# STM32.net
KiCad netlist of a schematic drawn in Altium Designer
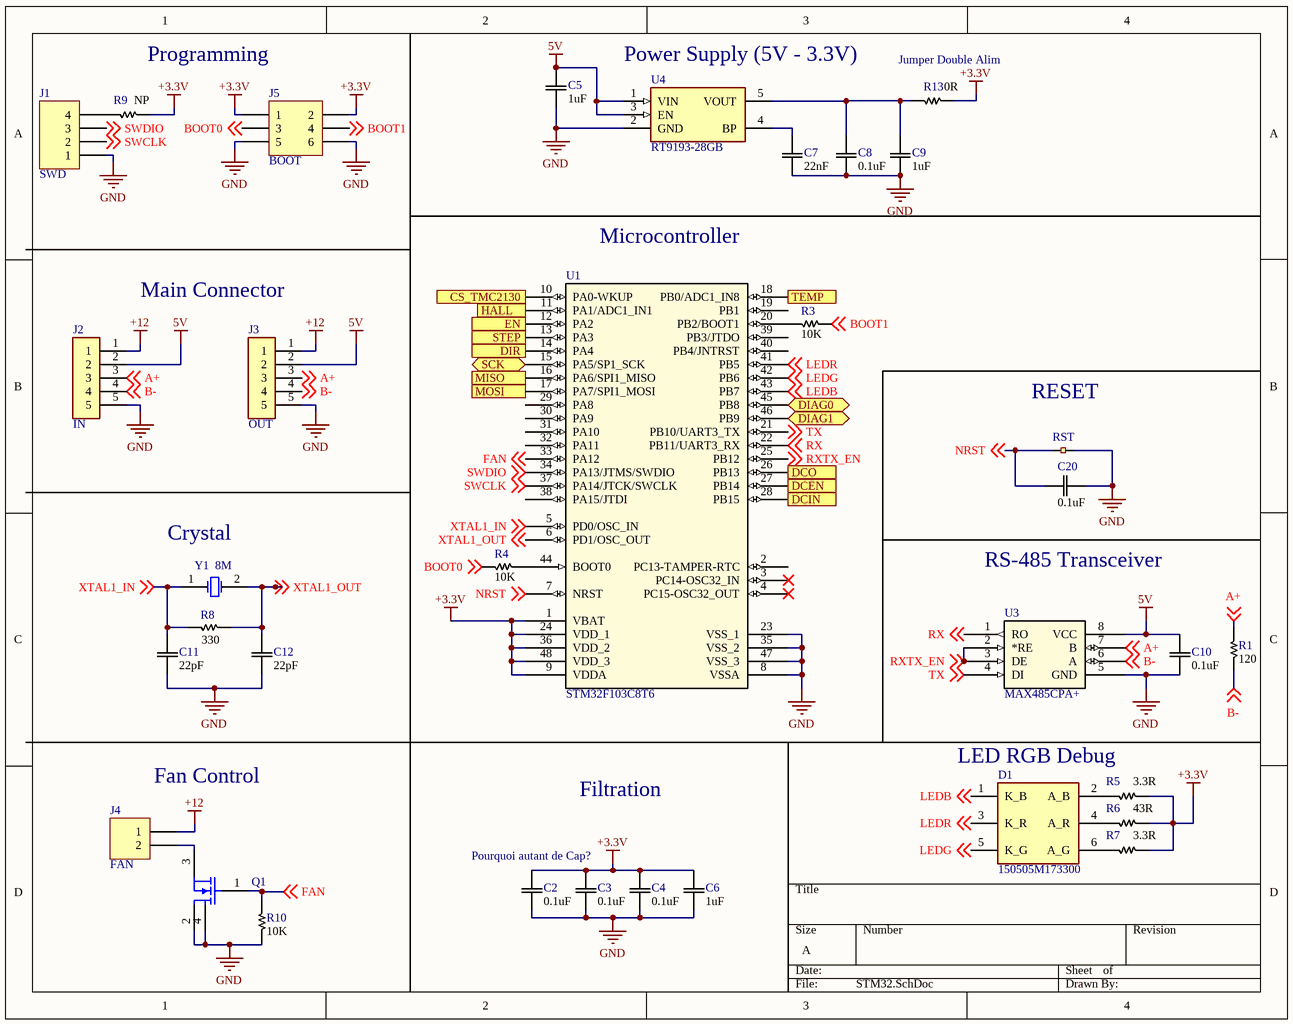
[diagram p0: STM32.SchDoc]

(export (version "E")
  (design (tool "Eeschema 10.0.6"))
  (components
    (comp (ref "C2")
      (value "0.1uF")
      (footprint "0603")
      (description "Capacitor SMD 1206")
      (fields
        (field (name "MANUFACTURER_PART_NUMBER") "12065A820JAT2A")
        (field (name "Comment") "Capacitor 1206")
        (field (name "COPYRIGHT") "Copyright (C) 2018 Accelerated Designs. All rights reserved")
      )
      (libsource (lib "Schematic_Emile") (part "Capacitor 1206"))
    )
    (comp (ref "C3")
      (value "0.1uF")
      (footprint "0603")
      (description "Capacitor SMD 1206")
      (fields
        (field (name "MANUFACTURER_PART_NUMBER") "12065A820JAT2A")
        (field (name "Comment") "Capacitor 1206")
        (field (name "COPYRIGHT") "Copyright (C) 2018 Accelerated Designs. All rights reserved")
      )
      (libsource (lib "Schematic_Emile") (part "Capacitor 1206"))
    )
    (comp (ref "C4")
      (value "0.1uF")
      (footprint "0603")
      (description "Capacitor SMD 1206")
      (fields
        (field (name "MANUFACTURER_PART_NUMBER") "12065A820JAT2A")
        (field (name "Comment") "Capacitor 1206")
        (field (name "COPYRIGHT") "Copyright (C) 2018 Accelerated Designs. All rights reserved")
      )
      (libsource (lib "Schematic_Emile") (part "Capacitor 1206"))
    )
    (comp (ref "C5")
      (value "1uF")
      (footprint "0603")
      (description "Capacitor SMD 1206")
      (fields
        (field (name "MANUFACTURER_PART_NUMBER") "12065A820JAT2A")
        (field (name "Comment") "Capacitor 1206")
        (field (name "COPYRIGHT") "Copyright (C) 2018 Accelerated Designs. All rights reserved")
      )
      (libsource (lib "Schematic_Emile") (part "Capacitor 1206"))
    )
    (comp (ref "C6")
      (value "1uF")
      (footprint "0603")
      (description "Capacitor SMD 1206")
      (fields
        (field (name "MANUFACTURER_PART_NUMBER") "12065A820JAT2A")
        (field (name "Comment") "Capacitor 1206")
        (field (name "COPYRIGHT") "Copyright (C) 2018 Accelerated Designs. All rights reserved")
      )
      (libsource (lib "Schematic_Emile") (part "Capacitor 1206"))
    )
    (comp (ref "C7")
      (value "22nF")
      (footprint "0603")
      (description "Capacitor SMD 1206")
      (fields
        (field (name "MANUFACTURER_PART_NUMBER") "12065A820JAT2A")
        (field (name "Comment") "Capacitor 1206")
        (field (name "COPYRIGHT") "Copyright (C) 2018 Accelerated Designs. All rights reserved")
      )
      (libsource (lib "Schematic_Emile") (part "Capacitor 1206"))
    )
    (comp (ref "C8")
      (value "0.1uF")
      (footprint "0603")
      (description "Capacitor SMD 1206")
      (fields
        (field (name "MANUFACTURER_PART_NUMBER") "12065A820JAT2A")
        (field (name "Comment") "Capacitor 1206")
        (field (name "COPYRIGHT") "Copyright (C) 2018 Accelerated Designs. All rights reserved")
      )
      (libsource (lib "Schematic_Emile") (part "Capacitor 1206"))
    )
    (comp (ref "C9")
      (value "1uF")
      (footprint "0603")
      (description "Capacitor SMD 1206")
      (fields
        (field (name "MANUFACTURER_PART_NUMBER") "12065A820JAT2A")
        (field (name "Comment") "Capacitor 1206")
        (field (name "COPYRIGHT") "Copyright (C) 2018 Accelerated Designs. All rights reserved")
      )
      (libsource (lib "Schematic_Emile") (part "Capacitor 1206"))
    )
    (comp (ref "C10")
      (value "0.1uF")
      (footprint "0603")
      (description "Capacitor SMD 1206")
      (fields
        (field (name "MANUFACTURER_PART_NUMBER") "12065A820JAT2A")
        (field (name "Comment") "Capacitor 1206")
        (field (name "COPYRIGHT") "Copyright (C) 2018 Accelerated Designs. All rights reserved")
      )
      (libsource (lib "Schematic_Emile") (part "Capacitor 1206"))
    )
    (comp (ref "C11")
      (value "22pF")
      (footprint "0603")
      (description "Capacitor SMD 1206")
      (fields
        (field (name "MANUFACTURER_PART_NUMBER") "12065A820JAT2A")
        (field (name "Comment") "Capacitor 1206")
        (field (name "COPYRIGHT") "Copyright (C) 2018 Accelerated Designs. All rights reserved")
      )
      (libsource (lib "Schematic_Emile") (part "Capacitor 1206"))
    )
    (comp (ref "C12")
      (value "22pF")
      (footprint "0603")
      (description "Capacitor SMD 1206")
      (fields
        (field (name "MANUFACTURER_PART_NUMBER") "12065A820JAT2A")
        (field (name "Comment") "Capacitor 1206")
        (field (name "COPYRIGHT") "Copyright (C) 2018 Accelerated Designs. All rights reserved")
      )
      (libsource (lib "Schematic_Emile") (part "Capacitor 1206"))
    )
    (comp (ref "C20")
      (value "0.1uF")
      (footprint "0603")
      (description "Capacitor SMD 1206")
      (fields
        (field (name "MANUFACTURER_PART_NUMBER") "12065A820JAT2A")
        (field (name "Comment") "Capacitor 1206")
        (field (name "COPYRIGHT") "Copyright (C) 2018 Accelerated Designs. All rights reserved")
      )
      (libsource (lib "Schematic_Emile") (part "Capacitor 1206"))
    )
    (comp (ref "D1")
      (value "150505M173300")
      (footprint "LED 5050")
      (description "LED")
      (fields
        (field (name "MOUSER PART NUMBER") "710-150505M173300")
        (field (name "RS PART NUMBER") "1766248P")
      )
      (libsource (lib "Schematic_Emile") (part "150505M173300"))
    )
    (comp (ref "J1")
      (value "SWD")
      (footprint "Header 4x1 1.277mm SMD")
      (description "Header, 4-Pin")
      (fields (field (name "PUBLISHER") "Altium Limited"))
      (libsource (lib "Miscellaneous Connectors") (part "Header 4"))
    )
    (comp (ref "J2")
      (value "IN")
      (footprint "JST 5POS 2.5mm 90°")
      (description "Connector")
      (fields (field (name "MANUFACTURER_PART_NUMBER") "S5B-XH-A-1(LF)(SN)"))
      (libsource (lib "Schematic_Emile") (part "JST 5POS"))
    )
    (comp (ref "J3")
      (value "OUT")
      (footprint "JST 5POS 2.5mm 90°")
      (description "Connector")
      (fields (field (name "MANUFACTURER_PART_NUMBER") "S5B-XH-A-1(LF)(SN)"))
      (libsource (lib "Schematic_Emile") (part "JST 5POS"))
    )
    (comp (ref "J4")
      (value "FAN")
      (footprint "HDR1X2")
      (description "Header, 2-Pin")
      (fields (field (name "PUBLISHER") "Altium Limited"))
      (libsource (lib "Miscellaneous Connectors") (part "Header 2"))
    )
    (comp (ref "J5")
      (value "BOOT")
      (footprint "Header 3x2 1.27mm SMD")
      (description "Header, 3-Pin, Dual row")
      (fields (field (name "PUBLISHER") "Altium Limited"))
      (libsource (lib "Miscellaneous Connectors") (part "Header 3X2"))
    )
    (comp (ref "Q1")
      (value "MOSFET N-CH")
      (footprint "SOT223_M")
      (description "55V 7A SOT223")
      (libsource (lib "Schematic_Emile") (part "MOSFET N-CH"))
    )
    (comp (ref "R1")
      (value "120")
      (footprint "0603")
      (description "Resistor 0603 SMD")
      (fields
        (field (name "MANUFACTURER_PART_NUMBER") "ERJ8CWFR024V")
        (field (name "Comment") "Resistor 0603")
        (field (name "COPYRIGHT") "Copyright (C) 2018 Accelerated Designs. All rights reserved")
      )
      (libsource (lib "Schematic_Emile") (part "Resistor 1206"))
    )
    (comp (ref "R3")
      (value "10K")
      (footprint "0603")
      (description "Resistor 1206 SMD")
      (fields
        (field (name "MANUFACTURER_PART_NUMBER") "ERJ8CWFR024V")
        (field (name "Comment") "Resistor 1206")
        (field (name "COPYRIGHT") "Copyright (C) 2018 Accelerated Designs. All rights reserved")
      )
      (libsource (lib "Schematic_Emile") (part "Resistor 1206"))
    )
    (comp (ref "R4")
      (value "10K")
      (footprint "0603")
      (description "Resistor 1206 SMD")
      (fields
        (field (name "MANUFACTURER_PART_NUMBER") "ERJ8CWFR024V")
        (field (name "Comment") "Resistor 1206")
        (field (name "COPYRIGHT") "Copyright (C) 2018 Accelerated Designs. All rights reserved")
      )
      (libsource (lib "Schematic_Emile") (part "Resistor 1206"))
    )
    (comp (ref "R5")
      (value "3.3R")
      (footprint "0603")
      (description "Resistor 0603 SMD")
      (fields
        (field (name "MANUFACTURER_PART_NUMBER") "ERJ8CWFR024V")
        (field (name "Comment") "Resistor 0603")
        (field (name "COPYRIGHT") "Copyright (C) 2018 Accelerated Designs. All rights reserved")
      )
      (libsource (lib "Schematic_Emile") (part "Resistor 1206"))
    )
    (comp (ref "R6")
      (value "43R")
      (footprint "0603")
      (description "Resistor 0603 SMD")
      (fields
        (field (name "MANUFACTURER_PART_NUMBER") "ERJ8CWFR024V")
        (field (name "Comment") "Resistor 0603")
        (field (name "COPYRIGHT") "Copyright (C) 2018 Accelerated Designs. All rights reserved")
      )
      (libsource (lib "Schematic_Emile") (part "Resistor 1206"))
    )
    (comp (ref "R7")
      (value "3.3R")
      (footprint "0603")
      (description "Resistor 0603 SMD")
      (fields
        (field (name "MANUFACTURER_PART_NUMBER") "ERJ8CWFR024V")
        (field (name "Comment") "Resistor 0603")
        (field (name "COPYRIGHT") "Copyright (C) 2018 Accelerated Designs. All rights reserved")
      )
      (libsource (lib "Schematic_Emile") (part "Resistor 1206"))
    )
    (comp (ref "R8")
      (value "330")
      (footprint "0603")
      (description "Resistor 0603 SMD")
      (fields
        (field (name "MANUFACTURER_PART_NUMBER") "ERJ8CWFR024V")
        (field (name "Comment") "Resistor 0603")
        (field (name "COPYRIGHT") "Copyright (C) 2018 Accelerated Designs. All rights reserved")
      )
      (libsource (lib "Schematic_Emile") (part "Resistor 1206"))
    )
    (comp (ref "R9")
      (value "NP")
      (footprint "0603")
      (description "Resistor 1206 SMD")
      (fields
        (field (name "MANUFACTURER_PART_NUMBER") "ERJ8CWFR024V")
        (field (name "Comment") "Jumper 0603")
        (field (name "COPYRIGHT") "Copyright (C) 2018 Accelerated Designs. All rights reserved")
      )
      (libsource (lib "Schematic_Emile") (part "Resistor 1206"))
    )
    (comp (ref "R10")
      (value "10K")
      (footprint "0603")
      (description "Resistor 0603 SMD")
      (fields
        (field (name "MANUFACTURER_PART_NUMBER") "ERJ8CWFR024V")
        (field (name "Comment") "Resistor 0603")
        (field (name "COPYRIGHT") "Copyright (C) 2018 Accelerated Designs. All rights reserved")
      )
      (libsource (lib "Schematic_Emile") (part "Resistor 1206"))
    )
    (comp (ref "R13")
      (value "0R")
      (footprint "0603")
      (description "Resistor 1206 SMD")
      (fields
        (field (name "MANUFACTURER_PART_NUMBER") "ERJ8CWFR024V")
        (field (name "Comment") "Jumper 0603")
        (field (name "COPYRIGHT") "Copyright (C) 2018 Accelerated Designs. All rights reserved")
      )
      (libsource (lib "Schematic_Emile") (part "Resistor 1206"))
    )
    (comp (ref "RST")
      (value "PAD")
      (footprint "PAD")
      (description "SMD Pad for contact")
      (libsource (lib "Schematic_Emile") (part "PAD"))
    )
    (comp (ref "U1")
      (value "STM32F103C8T6")
      (footprint "LQFP-48")
      (description "Integrated Circuit STM32")
      (fields (field (name "COPYRIGHT") "Copyright (C) 2018 Accelerated Designs. All rights reserved"))
      (libsource (lib "Schematic_Emile") (part "STM32F103C8T6"))
    )
    (comp (ref "U3")
      (value "MAX485CPA+")
      (footprint "DIP 8 - 3D")
      (description "RS485 Communication")
      (fields (field (name "COPYRIGHT") "Copyright (C) 2018 Accelerated Designs. All rights reserved"))
      (libsource (lib "Schematic_Emile") (part "MAX485CPA+"))
    )
    (comp (ref "U4")
      (value "RT9193-28GB")
      (footprint "SamacSys:SOT94P279X130-5N")
      (description "Voltage Regulator 3.3V")
      (libsource (lib "Schematic_Emile") (part "RT9193-28GB"))
    )
    (comp (ref "Y1")
      (value "8M")
      (footprint "ATS080B-E")
      (description "Crystal Oscillator")
      (fields (field (name "PUBLISHER") "Altium Limited"))
      (libsource (lib "Miscellaneous Devices") (part "XTAL"))
    )
  )
  (nets
    (net (code "1") (name "+3.3V") (class "Default")
      (node (ref "C2") (pin "2") (pinfunction "2_2") (pintype "passive"))
      (node (ref "C3") (pin "2") (pinfunction "2_2") (pintype "passive"))
      (node (ref "C4") (pin "2") (pinfunction "2_2") (pintype "passive"))
      (node (ref "C6") (pin "2") (pinfunction "2_2") (pintype "passive"))
      (node (ref "J5") (pin "1") (pinfunction "1_1") (pintype "passive"))
      (node (ref "J5") (pin "2") (pinfunction "2_2") (pintype "passive"))
      (node (ref "R13") (pin "2") (pinfunction "2_2") (pintype "passive"))
      (node (ref "R5") (pin "2") (pinfunction "2_2") (pintype "passive"))
      (node (ref "R6") (pin "2") (pinfunction "2_2") (pintype "passive"))
      (node (ref "R7") (pin "2") (pinfunction "2_2") (pintype "passive"))
      (node (ref "R9") (pin "2") (pinfunction "2_2") (pintype "passive"))
      (node (ref "U1") (pin "1") (pinfunction "VBAT_1") (pintype "power_in"))
      (node (ref "U1") (pin "24") (pinfunction "VDD_1_24") (pintype "power_in"))
      (node (ref "U1") (pin "36") (pinfunction "VDD_2_36") (pintype "power_in"))
      (node (ref "U1") (pin "48") (pinfunction "VDD_3_48") (pintype "power_in"))
      (node (ref "U1") (pin "9") (pinfunction "VDDA_9") (pintype "power_in"))
    )
    (net (code "2") (name "+12") (class "Default")
      (node (ref "J2") (pin "1") (pinfunction "1_1") (pintype "passive"))
      (node (ref "J3") (pin "1") (pinfunction "1_1") (pintype "passive"))
      (node (ref "J4") (pin "1") (pinfunction "1_1") (pintype "passive"))
    )
    (net (code "3") (name "/CS_TMC2130") (class "Default")
      (node (ref "U1") (pin "10") (pinfunction "PA0-WKUP_10") (pintype "bidirectional"))
    )
    (net (code "4") (name "/DCEN") (class "Default")
      (node (ref "U1") (pin "27") (pinfunction "PB14_27") (pintype "bidirectional"))
    )
    (net (code "5") (name "/DCIN") (class "Default")
      (node (ref "U1") (pin "28") (pinfunction "PB15_28") (pintype "bidirectional"))
    )
    (net (code "6") (name "/DCO") (class "Default")
      (node (ref "U1") (pin "26") (pinfunction "PB13_26") (pintype "bidirectional"))
    )
    (net (code "7") (name "/DIAG0") (class "Default")
      (node (ref "U1") (pin "45") (pinfunction "PB8_45") (pintype "bidirectional"))
    )
    (net (code "8") (name "/DIAG1") (class "Default")
      (node (ref "U1") (pin "46") (pinfunction "PB9_46") (pintype "bidirectional"))
    )
    (net (code "9") (name "/DIR") (class "Default")
      (node (ref "U1") (pin "14") (pinfunction "PA4_14") (pintype "bidirectional"))
    )
    (net (code "10") (name "/EN") (class "Default")
      (node (ref "U1") (pin "12") (pinfunction "PA2_12") (pintype "bidirectional"))
    )
    (net (code "11") (name "/HALL") (class "Default")
      (node (ref "U1") (pin "11") (pinfunction "PA1/ADC1_IN1_11") (pintype "bidirectional"))
    )
    (net (code "12") (name "/MISO") (class "Default")
      (node (ref "U1") (pin "16") (pinfunction "PA6/SPI1_MISO_16") (pintype "bidirectional"))
    )
    (net (code "13") (name "/MOSI") (class "Default")
      (node (ref "U1") (pin "17") (pinfunction "PA7/SPI1_MOSI_17") (pintype "bidirectional"))
    )
    (net (code "14") (name "/SCK") (class "Default")
      (node (ref "U1") (pin "15") (pinfunction "PA5/SP1_SCK_15") (pintype "bidirectional"))
    )
    (net (code "15") (name "/STEP") (class "Default")
      (node (ref "U1") (pin "13") (pinfunction "PA3_13") (pintype "bidirectional"))
    )
    (net (code "16") (name "/TEMP") (class "Default")
      (node (ref "U1") (pin "18") (pinfunction "PB0/ADC1_IN8_18") (pintype "bidirectional"))
    )
    (net (code "17") (name "5V") (class "Default")
      (node (ref "C10") (pin "2") (pinfunction "2_2") (pintype "passive"))
      (node (ref "C5") (pin "2") (pinfunction "2_2") (pintype "passive"))
      (node (ref "J2") (pin "2") (pinfunction "2_2") (pintype "passive"))
      (node (ref "J3") (pin "2") (pinfunction "2_2") (pintype "passive"))
      (node (ref "U3") (pin "8") (pinfunction "VCC_8") (pintype "power_in"))
      (node (ref "U4") (pin "1") (pinfunction "VIN_1") (pintype "input"))
      (node (ref "U4") (pin "3") (pinfunction "EN_3") (pintype "input"))
    )
    (net (code "18") (name "A+") (class "Default")
      (node (ref "J2") (pin "3") (pinfunction "3_3") (pintype "passive"))
      (node (ref "J3") (pin "3") (pinfunction "3_3") (pintype "passive"))
      (node (ref "R1") (pin "2") (pinfunction "2_2") (pintype "passive"))
      (node (ref "U3") (pin "7") (pinfunction "B_7") (pintype "bidirectional"))
    )
    (net (code "19") (name "B-") (class "Default")
      (node (ref "J2") (pin "4") (pinfunction "4_4") (pintype "passive"))
      (node (ref "J3") (pin "4") (pinfunction "4_4") (pintype "passive"))
      (node (ref "R1") (pin "1") (pinfunction "1_1") (pintype "passive"))
      (node (ref "U3") (pin "6") (pinfunction "A_6") (pintype "bidirectional"))
    )
    (net (code "20") (name "BOOT0") (class "Default")
      (node (ref "J5") (pin "3") (pinfunction "3_3") (pintype "passive"))
      (node (ref "R4") (pin "1") (pinfunction "1_1") (pintype "passive"))
    )
    (net (code "21") (name "BOOT1") (class "Default")
      (node (ref "J5") (pin "4") (pinfunction "4_4") (pintype "passive"))
      (node (ref "R3") (pin "2") (pinfunction "2_2") (pintype "passive"))
    )
    (net (code "22") (name "FAN") (class "Default")
      (node (ref "Q1") (pin "1") (pinfunction "G_1") (pintype "passive"))
      (node (ref "R10") (pin "2") (pinfunction "2_2") (pintype "passive"))
      (node (ref "U1") (pin "33") (pinfunction "PA12_33") (pintype "bidirectional"))
    )
    (net (code "23") (name "GND") (class "Default")
      (node (ref "C10") (pin "1") (pinfunction "1_1") (pintype "passive"))
      (node (ref "C11") (pin "1") (pinfunction "1_1") (pintype "passive"))
      (node (ref "C12") (pin "1") (pinfunction "1_1") (pintype "passive"))
      (node (ref "C2") (pin "1") (pinfunction "1_1") (pintype "passive"))
      (node (ref "C20") (pin "1") (pinfunction "1_1") (pintype "passive"))
      (node (ref "C3") (pin "1") (pinfunction "1_1") (pintype "passive"))
      (node (ref "C4") (pin "1") (pinfunction "1_1") (pintype "passive"))
      (node (ref "C5") (pin "1") (pinfunction "1_1") (pintype "passive"))
      (node (ref "C6") (pin "1") (pinfunction "1_1") (pintype "passive"))
      (node (ref "C7") (pin "1") (pinfunction "1_1") (pintype "passive"))
      (node (ref "C8") (pin "1") (pinfunction "1_1") (pintype "passive"))
      (node (ref "C9") (pin "1") (pinfunction "1_1") (pintype "passive"))
      (node (ref "J1") (pin "1") (pinfunction "1_1") (pintype "passive"))
      (node (ref "J2") (pin "5") (pinfunction "5_5") (pintype "passive"))
      (node (ref "J3") (pin "5") (pinfunction "5_5") (pintype "passive"))
      (node (ref "J5") (pin "5") (pinfunction "5_5") (pintype "passive"))
      (node (ref "J5") (pin "6") (pinfunction "6_6") (pintype "passive"))
      (node (ref "Q1") (pin "2") (pinfunction "D_2") (pintype "passive"))
      (node (ref "Q1") (pin "4") (pinfunction "D_4") (pintype "passive"))
      (node (ref "R10") (pin "1") (pinfunction "1_1") (pintype "passive"))
      (node (ref "RST") (pin "1") (pinfunction "1_1") (pintype "passive"))
      (node (ref "U1") (pin "23") (pinfunction "VSS_1_23") (pintype "power_in"))
      (node (ref "U1") (pin "35") (pinfunction "VSS_2_35") (pintype "power_in"))
      (node (ref "U1") (pin "47") (pinfunction "VSS_3_47") (pintype "power_in"))
      (node (ref "U1") (pin "8") (pinfunction "VSSA_8") (pintype "power_in"))
      (node (ref "U3") (pin "5") (pinfunction "GND_5") (pintype "power_in"))
      (node (ref "U4") (pin "2") (pinfunction "GND_2") (pintype "power_in"))
    )
    (net (code "24") (name "LEDB") (class "Default")
      (node (ref "D1") (pin "1") (pinfunction "K_B_1") (pintype "passive"))
      (node (ref "U1") (pin "43") (pinfunction "PB7_43") (pintype "bidirectional"))
    )
    (net (code "25") (name "LEDG") (class "Default")
      (node (ref "D1") (pin "5") (pinfunction "K_G_5") (pintype "passive"))
      (node (ref "U1") (pin "42") (pinfunction "PB6_42") (pintype "bidirectional"))
    )
    (net (code "26") (name "LEDR") (class "Default")
      (node (ref "D1") (pin "3") (pinfunction "K_R_3") (pintype "passive"))
      (node (ref "U1") (pin "41") (pinfunction "PB5_41") (pintype "bidirectional"))
    )
    (net (code "27") (name "NRST") (class "Default")
      (node (ref "C20") (pin "2") (pinfunction "2_2") (pintype "passive"))
      (node (ref "RST") (pin "2") (pinfunction "2_2") (pintype "passive"))
      (node (ref "U1") (pin "7") (pinfunction "NRST_7") (pintype "bidirectional"))
    )
    (net (code "28") (name "Net-(D1-A_B)") (class "Default")
      (node (ref "D1") (pin "2") (pinfunction "A_B_2") (pintype "passive"))
      (node (ref "R5") (pin "1") (pinfunction "1_1") (pintype "passive"))
    )
    (net (code "29") (name "Net-(D1-A_G)") (class "Default")
      (node (ref "D1") (pin "6") (pinfunction "A_G_6") (pintype "passive"))
      (node (ref "R7") (pin "1") (pinfunction "1_1") (pintype "passive"))
    )
    (net (code "30") (name "Net-(D1-A_R)") (class "Default")
      (node (ref "D1") (pin "4") (pinfunction "A_R_4") (pintype "passive"))
      (node (ref "R6") (pin "1") (pinfunction "1_1") (pintype "passive"))
    )
    (net (code "31") (name "Net-(J1-Pad4)") (class "Default")
      (node (ref "J1") (pin "4") (pinfunction "4_4") (pintype "passive"))
      (node (ref "R9") (pin "1") (pinfunction "1_1") (pintype "passive"))
    )
    (net (code "32") (name "Net-(Q1-S)") (class "Default")
      (node (ref "J4") (pin "2") (pinfunction "2_2") (pintype "passive"))
      (node (ref "Q1") (pin "3") (pinfunction "S_3") (pintype "passive"))
    )
    (net (code "33") (name "Net-(U1-BOOT0)") (class "Default")
      (node (ref "R4") (pin "2") (pinfunction "2_2") (pintype "passive"))
      (node (ref "U1") (pin "44") (pinfunction "BOOT0_44") (pintype "input"))
    )
    (net (code "34") (name "Net-(U1-PB2{slash}BOOT1)") (class "Default")
      (node (ref "R3") (pin "1") (pinfunction "1_1") (pintype "passive"))
      (node (ref "U1") (pin "20") (pinfunction "PB2/BOOT1_20") (pintype "bidirectional"))
    )
    (net (code "35") (name "Net-(U4-BP)") (class "Default")
      (node (ref "C7") (pin "2") (pinfunction "2_2") (pintype "passive"))
      (node (ref "U4") (pin "4") (pinfunction "BP_4") (pintype "passive"))
    )
    (net (code "36") (name "Net-(U4-VOUT)") (class "Default")
      (node (ref "C8") (pin "2") (pinfunction "2_2") (pintype "passive"))
      (node (ref "C9") (pin "2") (pinfunction "2_2") (pintype "passive"))
      (node (ref "R13") (pin "1") (pinfunction "1_1") (pintype "passive"))
      (node (ref "U4") (pin "5") (pinfunction "VOUT_5") (pintype "passive"))
    )
    (net (code "37") (name "RX") (class "Default")
      (node (ref "U1") (pin "22") (pinfunction "PB11/UART3_RX_22") (pintype "bidirectional"))
      (node (ref "U3") (pin "1") (pinfunction "RO_1") (pintype "output"))
    )
    (net (code "38") (name "RXTX_EN") (class "Default")
      (node (ref "U1") (pin "25") (pinfunction "PB12_25") (pintype "bidirectional"))
      (node (ref "U3") (pin "2") (pinfunction "*RE_2") (pintype "input"))
      (node (ref "U3") (pin "3") (pinfunction "DE_3") (pintype "input"))
    )
    (net (code "39") (name "SWCLK") (class "Default")
      (node (ref "J1") (pin "2") (pinfunction "2_2") (pintype "passive"))
      (node (ref "U1") (pin "37") (pinfunction "PA14/JTCK/SWCLK_37") (pintype "bidirectional"))
    )
    (net (code "40") (name "SWDIO") (class "Default")
      (node (ref "J1") (pin "3") (pinfunction "3_3") (pintype "passive"))
      (node (ref "U1") (pin "34") (pinfunction "PA13/JTMS/SWDIO_34") (pintype "bidirectional"))
    )
    (net (code "41") (name "TX") (class "Default")
      (node (ref "U1") (pin "21") (pinfunction "PB10/UART3_TX_21") (pintype "bidirectional"))
      (node (ref "U3") (pin "4") (pinfunction "DI_4") (pintype "input"))
    )
    (net (code "42") (name "XTAL1_IN") (class "Default")
      (node (ref "C11") (pin "2") (pinfunction "2_2") (pintype "passive"))
      (node (ref "R8") (pin "1") (pinfunction "1_1") (pintype "passive"))
      (node (ref "U1") (pin "5") (pinfunction "PD0/OSC_IN_5") (pintype "bidirectional"))
      (node (ref "Y1") (pin "1") (pinfunction "OSC1_1") (pintype "passive"))
    )
    (net (code "43") (name "XTAL1_OUT") (class "Default")
      (node (ref "C12") (pin "2") (pinfunction "2_2") (pintype "passive"))
      (node (ref "R8") (pin "2") (pinfunction "2_2") (pintype "passive"))
      (node (ref "U1") (pin "6") (pinfunction "PD1/OSC_OUT_6") (pintype "bidirectional"))
      (node (ref "Y1") (pin "2") (pinfunction "OSC2_2") (pintype "passive"))
    )
    (net (code "44") (name "unconnected-(U1-PA8-Pad29)") (class "Default")
      (node (ref "U1") (pin "29") (pinfunction "PA8_29") (pintype "bidirectional"))
    )
    (net (code "45") (name "unconnected-(U1-PA9-Pad30)") (class "Default")
      (node (ref "U1") (pin "30") (pinfunction "PA9_30") (pintype "bidirectional"))
    )
    (net (code "46") (name "unconnected-(U1-PA10-Pad31)") (class "Default")
      (node (ref "U1") (pin "31") (pinfunction "PA10_31") (pintype "bidirectional"))
    )
    (net (code "47") (name "unconnected-(U1-PA11-Pad32)") (class "Default")
      (node (ref "U1") (pin "32") (pinfunction "PA11_32") (pintype "bidirectional"))
    )
    (net (code "48") (name "unconnected-(U1-PA15{slash}JTDI-Pad38)") (class "Default")
      (node (ref "U1") (pin "38") (pinfunction "PA15/JTDI_38") (pintype "bidirectional"))
    )
    (net (code "49") (name "unconnected-(U1-PB1-Pad19)") (class "Default")
      (node (ref "U1") (pin "19") (pinfunction "PB1_19") (pintype "bidirectional"))
    )
    (net (code "50") (name "unconnected-(U1-PB3{slash}JTDO-Pad39)") (class "Default")
      (node (ref "U1") (pin "39") (pinfunction "PB3/JTDO_39") (pintype "bidirectional"))
    )
    (net (code "51") (name "unconnected-(U1-PB4{slash}JNTRST-Pad40)") (class "Default")
      (node (ref "U1") (pin "40") (pinfunction "PB4/JNTRST_40") (pintype "bidirectional"))
    )
    (net (code "52") (name "unconnected-(U1-PC13-TAMPER-RTC-Pad2)") (class "Default")
      (node (ref "U1") (pin "2") (pinfunction "PC13-TAMPER-RTC_2") (pintype "bidirectional"))
    )
    (net (code "53") (name "unconnected-(U1-PC14-OSC32_IN-Pad3)") (class "Default")
      (node (ref "U1") (pin "3") (pinfunction "PC14-OSC32_IN_3") (pintype "bidirectional+no_connect"))
    )
    (net (code "54") (name "unconnected-(U1-PC15-OSC32_OUT-Pad4)") (class "Default")
      (node (ref "U1") (pin "4") (pinfunction "PC15-OSC32_OUT_4") (pintype "bidirectional+no_connect"))
    )
  )
)
